# lightdimmer_pot.net
KiCad netlist of a schematic drawn in EAGLE
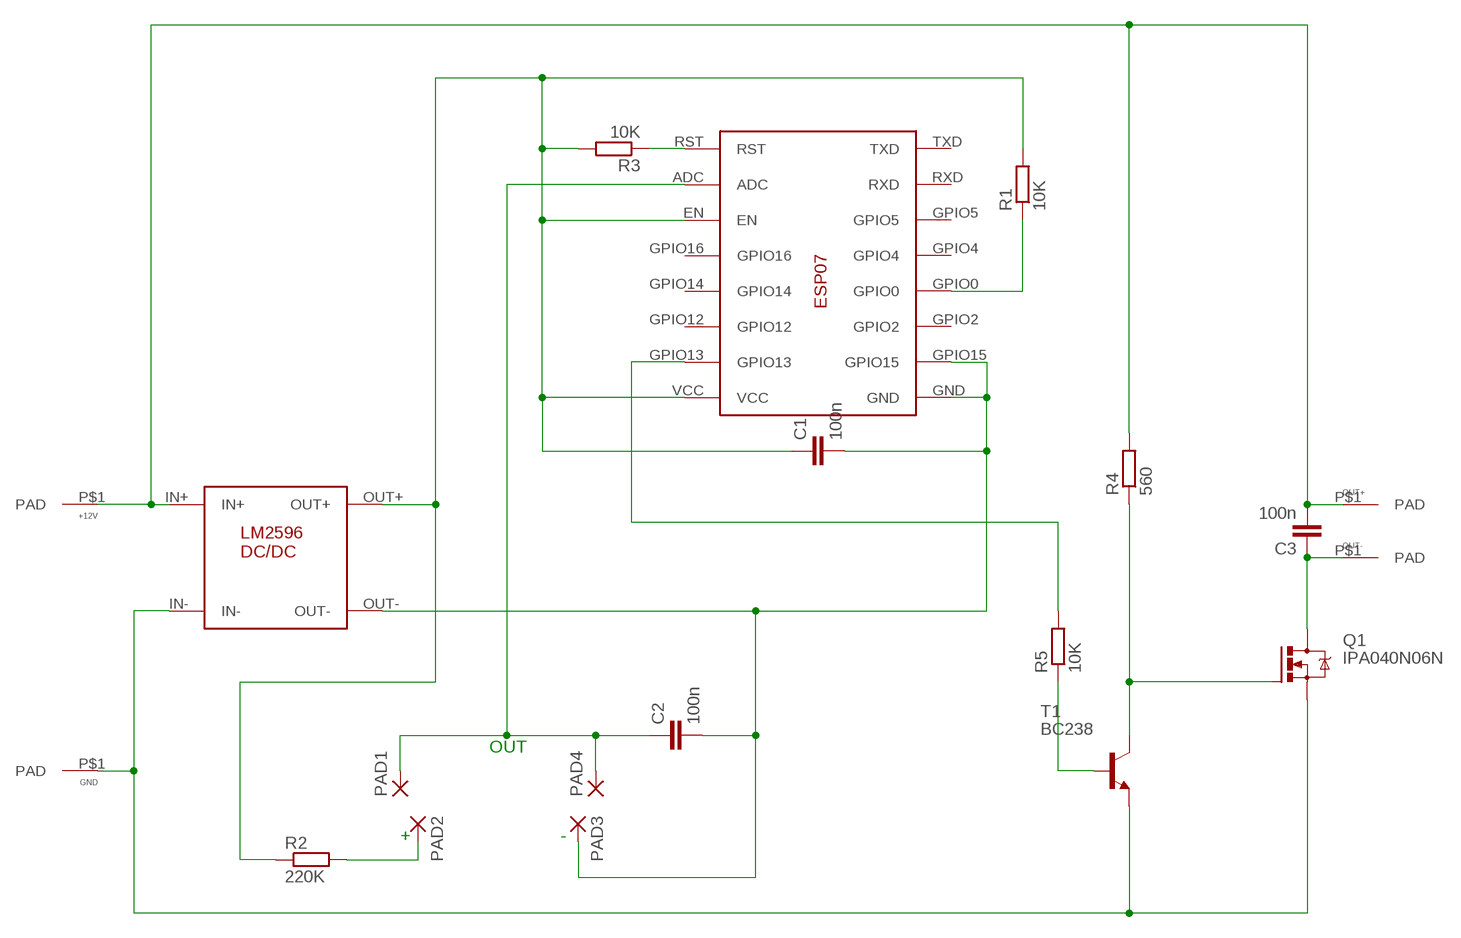
[diagram p0: schematic, sheet 1]

(export (version "E")
  (design (tool "Eeschema 10.0.6"))
  (components
    (comp (ref "+12V")
      (value "PAD")
      (footprint "eagle-import:PAD")
      (libsource (lib "eagle-import") (part "PAD"))
    )
    (comp (ref "C1")
      (value "100n")
      (footprint "eagle-import:C050-025X075")
      (libsource (lib "eagle-import") (part "C-EU050-025X075"))
    )
    (comp (ref "C2")
      (value "100n")
      (footprint "eagle-import:C050-025X075")
      (libsource (lib "eagle-import") (part "C-EU050-025X075"))
    )
    (comp (ref "C3")
      (value "100n")
      (footprint "eagle-import:C050-025X075")
      (libsource (lib "eagle-import") (part "C-EU050-025X075"))
    )
    (comp (ref "GND")
      (value "PAD")
      (footprint "eagle-import:PAD")
      (libsource (lib "eagle-import") (part "PAD"))
    )
    (comp (ref "OUT+")
      (value "PAD")
      (footprint "eagle-import:PAD")
      (libsource (lib "eagle-import") (part "PAD"))
    )
    (comp (ref "OUT-")
      (value "PAD")
      (footprint "eagle-import:PAD")
      (libsource (lib "eagle-import") (part "PAD"))
    )
    (comp (ref "PAD1")
      (value "WIREPAD3,17/1,1")
      (footprint "eagle-import:3,17_1,1")
      (libsource (lib "eagle-import") (part "WIREPAD3,17/1,1"))
    )
    (comp (ref "PAD2")
      (value "WIREPAD3,17/1,1")
      (footprint "eagle-import:3,17_1,1")
      (libsource (lib "eagle-import") (part "WIREPAD3,17/1,1"))
    )
    (comp (ref "PAD3")
      (value "WIREPAD3,17/1,1")
      (footprint "eagle-import:3,17_1,1")
      (libsource (lib "eagle-import") (part "WIREPAD3,17/1,1"))
    )
    (comp (ref "PAD4")
      (value "WIREPAD3,17/1,1")
      (footprint "eagle-import:3,17_1,1")
      (libsource (lib "eagle-import") (part "WIREPAD3,17/1,1"))
    )
    (comp (ref "Q1")
      (value "IPA040N06N")
      (footprint "eagle-import:TO220BV")
      (libsource (lib "eagle-import") (part "IRF520"))
    )
    (comp (ref "R1")
      (value "10K")
      (footprint "eagle-import:0204_7")
      (libsource (lib "eagle-import") (part "R-EU_0204/7"))
    )
    (comp (ref "R2")
      (value "220K")
      (footprint "eagle-import:0204_7")
      (libsource (lib "eagle-import") (part "R-EU_0204/7"))
    )
    (comp (ref "R3")
      (value "10K")
      (footprint "eagle-import:0204_7")
      (libsource (lib "eagle-import") (part "R-EU_0204/7"))
    )
    (comp (ref "R4")
      (value "560")
      (footprint "eagle-import:0204_7")
      (libsource (lib "eagle-import") (part "R-EU_0204/7"))
    )
    (comp (ref "R5")
      (value "10K")
      (footprint "eagle-import:0204_7")
      (libsource (lib "eagle-import") (part "R-EU_0204/7"))
    )
    (comp (ref "T1")
      (value "BC238")
      (footprint "eagle-import:TO92-CBE")
      (libsource (lib "eagle-import") (part "-NPN-TO92-CBEBC238"))
    )
    (comp (ref "U$1")
      (value "LM2596DCDC")
      (footprint "eagle-import:LM2596DCDC")
      (libsource (lib "eagle-import") (part "LM2596DCDC"))
    )
    (comp (ref "U$2")
      (value "ESP07")
      (footprint "eagle-import:ESP07")
      (libsource (lib "eagle-import") (part "ESP07"))
    )
  )
  (nets
    (net (code "1") (name "Net-(+12V-PAD)") (class "Default")
      (node (ref "+12V") (pin "P$1") (pinfunction "PAD_P$1") (pintype "bidirectional"))
      (node (ref "C3") (pin "2") (pinfunction "2_2") (pintype "passive"))
      (node (ref "OUT+") (pin "P$1") (pinfunction "PAD_P$1") (pintype "bidirectional"))
      (node (ref "R4") (pin "2") (pinfunction "2_2") (pintype "passive"))
      (node (ref "U$1") (pin "IN+") (pinfunction "IN+_IN+") (pintype "bidirectional"))
    )
    (net (code "2") (name "Net-(C1-Pad1)") (class "Default")
      (node (ref "C1") (pin "1") (pinfunction "1_1") (pintype "passive"))
      (node (ref "R1") (pin "2") (pinfunction "2_2") (pintype "passive"))
      (node (ref "R2") (pin "1") (pinfunction "1_1") (pintype "passive"))
      (node (ref "R3") (pin "2") (pinfunction "2_2") (pintype "passive"))
      (node (ref "U$1") (pin "OUT+") (pinfunction "OUT+_OUT+") (pintype "bidirectional"))
      (node (ref "U$2") (pin "EN") (pinfunction "EN_EN") (pintype "bidirectional"))
      (node (ref "U$2") (pin "VCC") (pinfunction "VCC_VCC") (pintype "bidirectional"))
    )
    (net (code "3") (name "Net-(GND-PAD)") (class "Default")
      (node (ref "GND") (pin "P$1") (pinfunction "PAD_P$1") (pintype "bidirectional"))
      (node (ref "Q1") (pin "S") (pinfunction "S_S") (pintype "passive"))
      (node (ref "T1") (pin "E") (pinfunction "E_E") (pintype "passive"))
      (node (ref "U$1") (pin "IN-") (pinfunction "IN-_IN-") (pintype "bidirectional"))
    )
    (net (code "4") (name "Net-(OUT--PAD)") (class "Default")
      (node (ref "C3") (pin "1") (pinfunction "1_1") (pintype "passive"))
      (node (ref "OUT-") (pin "P$1") (pinfunction "PAD_P$1") (pintype "bidirectional"))
      (node (ref "Q1") (pin "D") (pinfunction "D_D") (pintype "passive"))
    )
    (net (code "5") (name "Net-(PAD1-P)") (class "Default")
      (node (ref "C2") (pin "1") (pinfunction "1_1") (pintype "passive"))
      (node (ref "PAD1") (pin "1") (pinfunction "P_1") (pintype "passive"))
      (node (ref "PAD4") (pin "1") (pinfunction "P_1") (pintype "passive"))
      (node (ref "U$2") (pin "ADC") (pinfunction "ADC_ADC") (pintype "bidirectional"))
    )
    (net (code "6") (name "Net-(PAD2-P)") (class "Default")
      (node (ref "PAD2") (pin "1") (pinfunction "P_1") (pintype "passive"))
      (node (ref "R2") (pin "2") (pinfunction "2_2") (pintype "passive"))
    )
    (net (code "7") (name "Net-(PAD3-P)") (class "Default")
      (node (ref "C1") (pin "2") (pinfunction "2_2") (pintype "passive"))
      (node (ref "C2") (pin "2") (pinfunction "2_2") (pintype "passive"))
      (node (ref "PAD3") (pin "1") (pinfunction "P_1") (pintype "passive"))
      (node (ref "U$1") (pin "OUT-") (pinfunction "OUT-_OUT-") (pintype "bidirectional"))
      (node (ref "U$2") (pin "GND") (pinfunction "GND_GND") (pintype "bidirectional"))
      (node (ref "U$2") (pin "GPIO15") (pinfunction "GPIO15_GPIO15") (pintype "bidirectional"))
    )
    (net (code "8") (name "Net-(Q1-PadG)") (class "Default")
      (node (ref "Q1") (pin "G") (pinfunction "G_G") (pintype "passive"))
      (node (ref "R4") (pin "1") (pinfunction "1_1") (pintype "passive"))
      (node (ref "T1") (pin "C") (pinfunction "C_C") (pintype "passive"))
    )
    (net (code "9") (name "Net-(R1-Pad1)") (class "Default")
      (node (ref "R1") (pin "1") (pinfunction "1_1") (pintype "passive"))
      (node (ref "U$2") (pin "GPIO0") (pinfunction "GPIO0_GPIO0") (pintype "bidirectional"))
    )
    (net (code "10") (name "Net-(R3-Pad1)") (class "Default")
      (node (ref "R3") (pin "1") (pinfunction "1_1") (pintype "passive"))
      (node (ref "U$2") (pin "RST") (pinfunction "RST_RST") (pintype "bidirectional"))
    )
    (net (code "11") (name "Net-(R5-Pad1)") (class "Default")
      (node (ref "R5") (pin "1") (pinfunction "1_1") (pintype "passive"))
      (node (ref "T1") (pin "B") (pinfunction "B_B") (pintype "passive"))
    )
    (net (code "12") (name "Net-(R5-Pad2)") (class "Default")
      (node (ref "R5") (pin "2") (pinfunction "2_2") (pintype "passive"))
      (node (ref "U$2") (pin "GPIO13") (pinfunction "GPIO13_GPIO13") (pintype "bidirectional"))
    )
    (net (code "13") (name "unconnected-(U$2-PadGPIO2)") (class "Default")
      (node (ref "U$2") (pin "GPIO2") (pinfunction "GPIO2_GPIO2") (pintype "bidirectional"))
    )
    (net (code "14") (name "unconnected-(U$2-PadGPIO4)") (class "Default")
      (node (ref "U$2") (pin "GPIO4") (pinfunction "GPIO4_GPIO4") (pintype "bidirectional"))
    )
    (net (code "15") (name "unconnected-(U$2-PadGPIO5)") (class "Default")
      (node (ref "U$2") (pin "GPIO5") (pinfunction "GPIO5_GPIO5") (pintype "bidirectional"))
    )
    (net (code "16") (name "unconnected-(U$2-PadGPIO12)") (class "Default")
      (node (ref "U$2") (pin "GPIO12") (pinfunction "GPIO12_GPIO12") (pintype "bidirectional"))
    )
    (net (code "17") (name "unconnected-(U$2-PadGPIO14)") (class "Default")
      (node (ref "U$2") (pin "GPIO14") (pinfunction "GPIO14_GPIO14") (pintype "bidirectional"))
    )
    (net (code "18") (name "unconnected-(U$2-PadGPIO16)") (class "Default")
      (node (ref "U$2") (pin "GPIO16") (pinfunction "GPIO16_GPIO16") (pintype "bidirectional"))
    )
    (net (code "19") (name "unconnected-(U$2-PadRXD)") (class "Default")
      (node (ref "U$2") (pin "RXD") (pinfunction "RXD_RXD") (pintype "bidirectional"))
    )
    (net (code "20") (name "unconnected-(U$2-PadTXD)") (class "Default")
      (node (ref "U$2") (pin "TXD") (pinfunction "TXD_TXD") (pintype "bidirectional"))
    )
  )
)
